# Main.net
KiCad netlist of a schematic drawn in Altium Designer
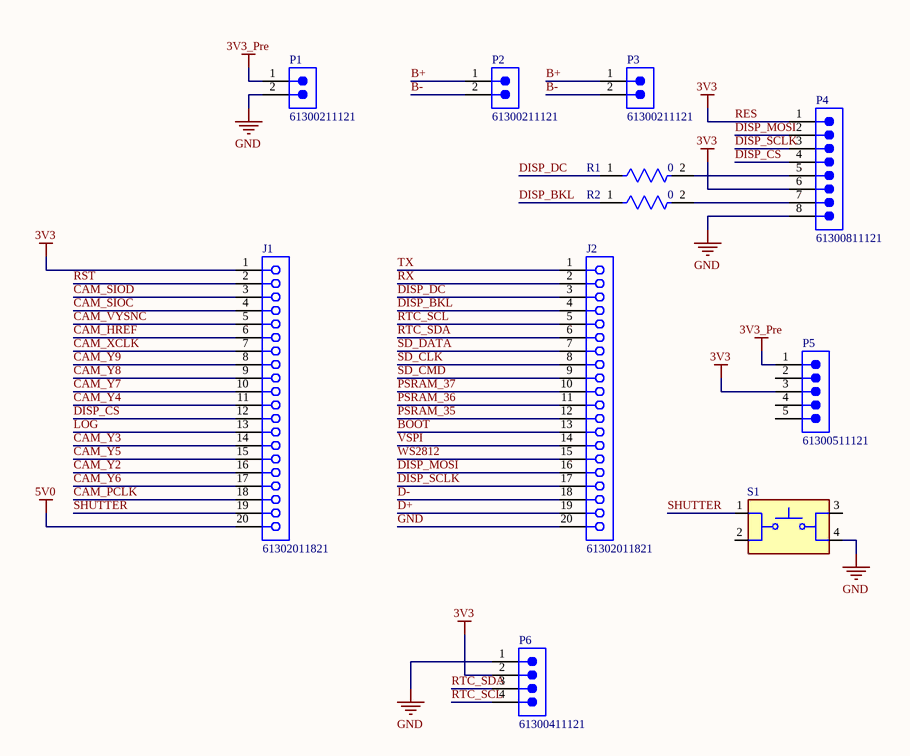
[diagram p0: Main.SchDoc]

(export (version "E")
  (design (tool "Eeschema 10.0.6"))
  (components
    (comp (ref "J1")
      (value "61302011821")
      (footprint "61302011821")
      (description "THT Vertical Socket Header WR-PHD, Pitch 2.54 mm, Single Row, 20 pins")
      (libsource (lib "Altium Content Vault") (part "Header_Female_1R_20P"))
    )
    (comp (ref "J2")
      (value "61302011821")
      (footprint "61302011821")
      (description "THT Vertical Socket Header WR-PHD, Pitch 2.54 mm, Single Row, 20 pins")
      (libsource (lib "Altium Content Vault") (part "Header_Female_1R_20P"))
    )
    (comp (ref "P1")
      (value "61300211121")
      (footprint "61300211121")
      (description "THT Vertical Pin Header WR-PHD, Pitch 2.54 mm, Single Row, 2 pins")
      (libsource (lib "Altium Content Vault") (part "Header_Male_1R_02P"))
    )
    (comp (ref "P2")
      (value "61300211121")
      (footprint "61300211121")
      (description "THT Vertical Pin Header WR-PHD, Pitch 2.54 mm, Single Row, 2 pins")
      (libsource (lib "Altium Content Vault") (part "Header_Male_1R_02P"))
    )
    (comp (ref "P3")
      (value "61300211121")
      (footprint "61300211121")
      (description "THT Vertical Pin Header WR-PHD, Pitch 2.54 mm, Single Row, 2 pins")
      (libsource (lib "Altium Content Vault") (part "Header_Male_1R_02P"))
    )
    (comp (ref "P4")
      (value "61300811121")
      (footprint "61300811121")
      (description "THT Vertical Pin Header WR-PHD, Pitch 2.54 mm, Single Row, 8 pins")
      (libsource (lib "Altium Content Vault") (part "Header_Male_1R_08P"))
    )
    (comp (ref "P5")
      (value "61300511121")
      (footprint "61300511121")
      (description "THT Vertical Pin Header WR-PHD, Pitch 2.54 mm, Single Row, 5 pins")
      (libsource (lib "Altium Content Vault") (part "Header_Male_1R_05P"))
    )
    (comp (ref "P6")
      (value "61300411121")
      (footprint "61300411121")
      (description "THT Vertical Pin Header WR-PHD, Pitch 2.54 mm, Single Row, 4 pins")
      (libsource (lib "Altium Content Vault") (part "Header_Male_1R_04P"))
    )
    (comp (ref "R1")
      (value "0")
      (footprint "FP-RMCF1206-IPC_C")
      (description "2.21kΩ ±1% 0.25W 1206 Thick Film Chip Resistor AEC-Q200 compliant")
      (fields (field (name "TOLERANCE") "1%"))
      (libsource (lib "Altium Content Vault") (part "1029c3af85768c4190bb7ad29bc67b5"))
    )
    (comp (ref "R2")
      (value "0")
      (footprint "FP-RMCF1206-IPC_C")
      (description "2.21kΩ ±1% 0.25W 1206 Thick Film Chip Resistor AEC-Q200 compliant")
      (fields (field (name "TOLERANCE") "1%"))
      (libsource (lib "Altium Content Vault") (part "1029c3af85768c4190bb7ad29bc67b5"))
    )
    (comp (ref "S1")
      (value "SWT0325-073016TSK_REVA")
      (footprint "SW_SWT0325-073016TSK_REVA")
      (description "6mm x 6mm Through Hole Tactile Switch")
      (fields (field (name "MF") "Global Connector Technology") (field (name "MP") "SWT0325-073016TSK"))
      (libsource (lib "SWT0325-073016TSK_REVA") (part "SWT0325-073016TSK_REVA"))
    )
  )
  (nets
    (net (code "1") (name "/B+") (class "Default")
      (node (ref "P2") (pin "1") (pinfunction "1_1") (pintype "passive"))
      (node (ref "P3") (pin "1") (pinfunction "1_1") (pintype "passive"))
    )
    (net (code "2") (name "/B-") (class "Default")
      (node (ref "P2") (pin "2") (pinfunction "2_2") (pintype "passive"))
      (node (ref "P3") (pin "2") (pinfunction "2_2") (pintype "passive"))
    )
    (net (code "3") (name "/BOOT") (class "Default")
      (node (ref "J2") (pin "13") (pinfunction "13_13") (pintype "passive"))
    )
    (net (code "4") (name "/CAM_HREF") (class "Default")
      (node (ref "J1") (pin "6") (pinfunction "6_6") (pintype "passive"))
    )
    (net (code "5") (name "/CAM_PCLK") (class "Default")
      (node (ref "J1") (pin "18") (pinfunction "18_18") (pintype "passive"))
    )
    (net (code "6") (name "/CAM_SIOC") (class "Default")
      (node (ref "J1") (pin "4") (pinfunction "4_4") (pintype "passive"))
    )
    (net (code "7") (name "/CAM_SIOD") (class "Default")
      (node (ref "J1") (pin "3") (pinfunction "3_3") (pintype "passive"))
    )
    (net (code "8") (name "/CAM_VYSNC") (class "Default")
      (node (ref "J1") (pin "5") (pinfunction "5_5") (pintype "passive"))
    )
    (net (code "9") (name "/CAM_XCLK") (class "Default")
      (node (ref "J1") (pin "7") (pinfunction "7_7") (pintype "passive"))
    )
    (net (code "10") (name "/CAM_Y2") (class "Default")
      (node (ref "J1") (pin "16") (pinfunction "16_16") (pintype "passive"))
    )
    (net (code "11") (name "/CAM_Y3") (class "Default")
      (node (ref "J1") (pin "14") (pinfunction "14_14") (pintype "passive"))
    )
    (net (code "12") (name "/CAM_Y4") (class "Default")
      (node (ref "J1") (pin "11") (pinfunction "11_11") (pintype "passive"))
    )
    (net (code "13") (name "/CAM_Y5") (class "Default")
      (node (ref "J1") (pin "15") (pinfunction "15_15") (pintype "passive"))
    )
    (net (code "14") (name "/CAM_Y6") (class "Default")
      (node (ref "J1") (pin "17") (pinfunction "17_17") (pintype "passive"))
    )
    (net (code "15") (name "/CAM_Y7") (class "Default")
      (node (ref "J1") (pin "10") (pinfunction "10_10") (pintype "passive"))
    )
    (net (code "16") (name "/CAM_Y8") (class "Default")
      (node (ref "J1") (pin "9") (pinfunction "9_9") (pintype "passive"))
    )
    (net (code "17") (name "/CAM_Y9") (class "Default")
      (node (ref "J1") (pin "8") (pinfunction "8_8") (pintype "passive"))
    )
    (net (code "18") (name "/D+") (class "Default")
      (node (ref "J2") (pin "19") (pinfunction "19_19") (pintype "passive"))
    )
    (net (code "19") (name "/D-") (class "Default")
      (node (ref "J2") (pin "18") (pinfunction "18_18") (pintype "passive"))
    )
    (net (code "20") (name "/DISP_BKL") (class "Default")
      (node (ref "J2") (pin "4") (pinfunction "4_4") (pintype "passive"))
      (node (ref "R2") (pin "1") (pinfunction "1_1") (pintype "passive"))
    )
    (net (code "21") (name "/DISP_CS") (class "Default")
      (node (ref "J1") (pin "12") (pinfunction "12_12") (pintype "passive"))
      (node (ref "P4") (pin "4") (pinfunction "4_4") (pintype "passive"))
    )
    (net (code "22") (name "/DISP_DC") (class "Default")
      (node (ref "J2") (pin "3") (pinfunction "3_3") (pintype "passive"))
      (node (ref "R1") (pin "1") (pinfunction "1_1") (pintype "passive"))
    )
    (net (code "23") (name "/DISP_MOSI") (class "Default")
      (node (ref "J2") (pin "16") (pinfunction "16_16") (pintype "passive"))
      (node (ref "P4") (pin "2") (pinfunction "2_2") (pintype "passive"))
    )
    (net (code "24") (name "/DISP_SCLK") (class "Default")
      (node (ref "J2") (pin "17") (pinfunction "17_17") (pintype "passive"))
      (node (ref "P4") (pin "3") (pinfunction "3_3") (pintype "passive"))
    )
    (net (code "25") (name "/LOG") (class "Default")
      (node (ref "J1") (pin "13") (pinfunction "13_13") (pintype "passive"))
    )
    (net (code "26") (name "/PSRAM_35") (class "Default")
      (node (ref "J2") (pin "12") (pinfunction "12_12") (pintype "passive"))
    )
    (net (code "27") (name "/PSRAM_36") (class "Default")
      (node (ref "J2") (pin "11") (pinfunction "11_11") (pintype "passive"))
    )
    (net (code "28") (name "/PSRAM_37") (class "Default")
      (node (ref "J2") (pin "10") (pinfunction "10_10") (pintype "passive"))
    )
    (net (code "29") (name "/RST") (class "Default")
      (node (ref "J1") (pin "2") (pinfunction "2_2") (pintype "passive"))
    )
    (net (code "30") (name "/RTC_SCL") (class "Default")
      (node (ref "J2") (pin "5") (pinfunction "5_5") (pintype "passive"))
      (node (ref "P6") (pin "4") (pinfunction "4_4") (pintype "passive"))
    )
    (net (code "31") (name "/RTC_SDA") (class "Default")
      (node (ref "J2") (pin "6") (pinfunction "6_6") (pintype "passive"))
      (node (ref "P6") (pin "3") (pinfunction "3_3") (pintype "passive"))
    )
    (net (code "32") (name "/RX") (class "Default")
      (node (ref "J2") (pin "2") (pinfunction "2_2") (pintype "passive"))
    )
    (net (code "33") (name "/SD_CLK") (class "Default")
      (node (ref "J2") (pin "8") (pinfunction "8_8") (pintype "passive"))
    )
    (net (code "34") (name "/SD_CMD") (class "Default")
      (node (ref "J2") (pin "9") (pinfunction "9_9") (pintype "passive"))
    )
    (net (code "35") (name "/SD_DATA") (class "Default")
      (node (ref "J2") (pin "7") (pinfunction "7_7") (pintype "passive"))
    )
    (net (code "36") (name "/SHUTTER") (class "Default")
      (node (ref "J1") (pin "19") (pinfunction "19_19") (pintype "passive"))
      (node (ref "S1") (pin "1") (pinfunction "1_1") (pintype "passive"))
    )
    (net (code "37") (name "/TX") (class "Default")
      (node (ref "J2") (pin "1") (pinfunction "1_1") (pintype "passive"))
    )
    (net (code "38") (name "/VSPI") (class "Default")
      (node (ref "J2") (pin "14") (pinfunction "14_14") (pintype "passive"))
    )
    (net (code "39") (name "/WS2812") (class "Default")
      (node (ref "J2") (pin "15") (pinfunction "15_15") (pintype "passive"))
    )
    (net (code "40") (name "3V3") (class "Default")
      (node (ref "J1") (pin "1") (pinfunction "1_1") (pintype "passive"))
      (node (ref "P4") (pin "1") (pinfunction "1_1") (pintype "passive"))
      (node (ref "P4") (pin "6") (pinfunction "6_6") (pintype "passive"))
      (node (ref "P5") (pin "3") (pinfunction "3_3") (pintype "passive"))
      (node (ref "P6") (pin "2") (pinfunction "2_2") (pintype "passive"))
    )
    (net (code "41") (name "3V3_Pre") (class "Default")
      (node (ref "P1") (pin "1") (pinfunction "1_1") (pintype "passive"))
      (node (ref "P5") (pin "1") (pinfunction "1_1") (pintype "passive"))
    )
    (net (code "42") (name "5V0") (class "Default")
      (node (ref "J1") (pin "20") (pinfunction "20_20") (pintype "passive"))
    )
    (net (code "43") (name "GND") (class "Default")
      (node (ref "J2") (pin "20") (pinfunction "20_20") (pintype "passive"))
      (node (ref "P1") (pin "2") (pinfunction "2_2") (pintype "passive"))
      (node (ref "P4") (pin "8") (pinfunction "8_8") (pintype "passive"))
      (node (ref "P6") (pin "1") (pinfunction "1_1") (pintype "passive"))
      (node (ref "S1") (pin "4") (pinfunction "4_4") (pintype "passive"))
    )
    (net (code "44") (name "Net-(P4-Pad5)") (class "Default")
      (node (ref "P4") (pin "5") (pinfunction "5_5") (pintype "passive"))
      (node (ref "R1") (pin "2") (pinfunction "2_2") (pintype "passive"))
    )
    (net (code "45") (name "Net-(P4-Pad7)") (class "Default")
      (node (ref "P4") (pin "7") (pinfunction "7_7") (pintype "passive"))
      (node (ref "R2") (pin "2") (pinfunction "2_2") (pintype "passive"))
    )
    (net (code "46") (name "unconnected-(P5-Pad2)") (class "Default")
      (node (ref "P5") (pin "2") (pinfunction "2_2") (pintype "passive"))
    )
    (net (code "47") (name "unconnected-(P5-Pad4)") (class "Default")
      (node (ref "P5") (pin "4") (pinfunction "4_4") (pintype "passive"))
    )
    (net (code "48") (name "unconnected-(P5-Pad5)") (class "Default")
      (node (ref "P5") (pin "5") (pinfunction "5_5") (pintype "passive"))
    )
    (net (code "49") (name "unconnected-(S1-Pad2)") (class "Default")
      (node (ref "S1") (pin "2") (pinfunction "2_2") (pintype "passive"))
    )
    (net (code "50") (name "unconnected-(S1-Pad3)") (class "Default")
      (node (ref "S1") (pin "3") (pinfunction "3_3") (pintype "passive"))
    )
  )
)
